# GD_supply.net
KiCad netlist of a schematic drawn in Altium Designer
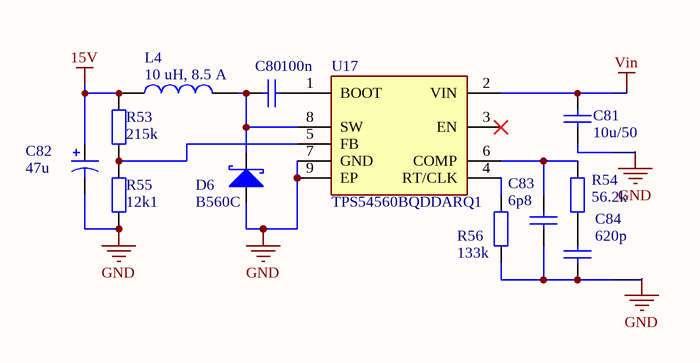
[diagram p0: GD_supply.SchDoc]

(export (version "E")
  (design (tool "Eeschema 10.0.6"))
  (components
    (comp (ref "C80")
      (value "100n")
      (footprint "C_0603")
      (description "cond")
      (libsource (lib "M_Standard") (part "C_MLCC"))
    )
    (comp (ref "C81")
      (value "10u/50")
      (footprint "C_1210")
      (description "cond")
      (libsource (lib "M_Standard") (part "C_MLCC"))
    )
    (comp (ref "C82")
      (value "47u")
      (footprint "C_SMD_R8*10 Elyt")
      (description "Polarized Capacitor")
      (libsource (lib "M_Standard") (part "C_Elyt"))
    )
    (comp (ref "C83")
      (value "6p8")
      (footprint "C_0603")
      (description "cond")
      (libsource (lib "M_Standard") (part "C_MLCC"))
    )
    (comp (ref "C84")
      (value "620p")
      (footprint "C_0603")
      (description "cond")
      (libsource (lib "M_Standard") (part "C_MLCC"))
    )
    (comp (ref "D6")
      (value "B560C")
      (footprint "D_DO214AB-SMC")
      (description "Schottky Diode")
      (libsource (lib "M_Standard") (part "D_Schottky"))
    )
    (comp (ref "L4")
      (value "10 uH, 8.5 A")
      (footprint "7443550101_Altium_WE-HCI_rev18a:WE-HCI_1350")
      (description "SMT Flat Wire High Current Inductor WE-HCI, size 1350, 10 uH, 8.5 A")
      (fields (field (name "PART NUMBER") "7443550101") (field (name "PUBLISHER") "Wurth Elektronik"))
      (libsource (lib "WE-HCI (rev18a)") (part "7443550101"))
    )
    (comp (ref "R53")
      (value "215k")
      (footprint "R_0603")
      (description "Resistor")
      (libsource (lib "M_Standard") (part "R_Uni"))
    )
    (comp (ref "R54")
      (value "56.2k")
      (footprint "R_0603")
      (description "Resistor")
      (libsource (lib "M_Standard") (part "R_Uni"))
    )
    (comp (ref "R55")
      (value "12k1")
      (footprint "R_0603")
      (description "Resistor")
      (libsource (lib "M_Standard") (part "R_Uni"))
    )
    (comp (ref "R56")
      (value "133k")
      (footprint "R_0603")
      (description "Resistor")
      (libsource (lib "M_Standard") (part "R_Uni"))
    )
    (comp (ref "U17")
      (value "TPS54560BQDDARQ1")
      (footprint "IC_TPS54560BQDDARQ1")
      (description "4.5 V to 60 V Input, 5 A, Step Down DC-DC Converter")
      (libsource (lib "M_Standard") (part "IC_TPS54560BQDDARQ1"))
    )
  )
  (nets
    (net (code "1") (name "15V") (class "Default")
      (node (ref "C82") (pin "1") (pinfunction "1_1") (pintype "passive"))
      (node (ref "L4") (pin "2") (pinfunction "2_2") (pintype "passive"))
      (node (ref "R53") (pin "2") (pinfunction "2_2") (pintype "passive"))
    )
    (net (code "2") (name "GND") (class "Default")
      (node (ref "C81") (pin "1") (pinfunction "1_1") (pintype "passive"))
      (node (ref "C82") (pin "2") (pinfunction "2_2") (pintype "passive"))
      (node (ref "C83") (pin "1") (pinfunction "1_1") (pintype "passive"))
      (node (ref "C84") (pin "1") (pinfunction "1_1") (pintype "passive"))
      (node (ref "D6") (pin "2") (pinfunction "A_2") (pintype "passive"))
      (node (ref "R55") (pin "1") (pinfunction "1_1") (pintype "passive"))
      (node (ref "R56") (pin "1") (pinfunction "1_1") (pintype "passive"))
      (node (ref "U17") (pin "7") (pinfunction "GND_7") (pintype "passive"))
      (node (ref "U17") (pin "9") (pinfunction "EP_9") (pintype "passive"))
    )
    (net (code "3") (name "Net-(C84-Pad2)") (class "Default")
      (node (ref "C84") (pin "2") (pinfunction "2_2") (pintype "passive"))
      (node (ref "R54") (pin "1") (pinfunction "1_1") (pintype "passive"))
    )
    (net (code "4") (name "Net-(D6-K)") (class "Default")
      (node (ref "C80") (pin "1") (pinfunction "1_1") (pintype "passive"))
      (node (ref "D6") (pin "1") (pinfunction "K_1") (pintype "passive"))
      (node (ref "L4") (pin "1") (pinfunction "1_1") (pintype "passive"))
      (node (ref "U17") (pin "8") (pinfunction "SW_8") (pintype "passive"))
    )
    (net (code "5") (name "Net-(U17-BOOT)") (class "Default")
      (node (ref "C80") (pin "2") (pinfunction "2_2") (pintype "passive"))
      (node (ref "U17") (pin "1") (pinfunction "BOOT_1") (pintype "passive"))
    )
    (net (code "6") (name "Net-(U17-COMP)") (class "Default")
      (node (ref "C83") (pin "2") (pinfunction "2_2") (pintype "passive"))
      (node (ref "R54") (pin "2") (pinfunction "2_2") (pintype "passive"))
      (node (ref "U17") (pin "6") (pinfunction "COMP_6") (pintype "passive"))
    )
    (net (code "7") (name "Net-(U17-FB)") (class "Default")
      (node (ref "R53") (pin "1") (pinfunction "1_1") (pintype "passive"))
      (node (ref "R55") (pin "2") (pinfunction "2_2") (pintype "passive"))
      (node (ref "U17") (pin "5") (pinfunction "FB_5") (pintype "passive"))
    )
    (net (code "8") (name "Net-(U17-RT{slash}CLK)") (class "Default")
      (node (ref "R56") (pin "2") (pinfunction "2_2") (pintype "passive"))
      (node (ref "U17") (pin "4") (pinfunction "RT/CLK_4") (pintype "passive"))
    )
    (net (code "9") (name "Vin") (class "Default")
      (node (ref "C81") (pin "2") (pinfunction "2_2") (pintype "passive"))
      (node (ref "U17") (pin "2") (pinfunction "VIN_2") (pintype "passive"))
    )
    (net (code "10") (name "unconnected-(U17-EN-Pad3)") (class "Default")
      (node (ref "U17") (pin "3") (pinfunction "EN_3") (pintype "passive+no_connect"))
    )
  )
)
